# M5stamp_round_lcd.net
KiCad netlist of a schematic drawn in EAGLE
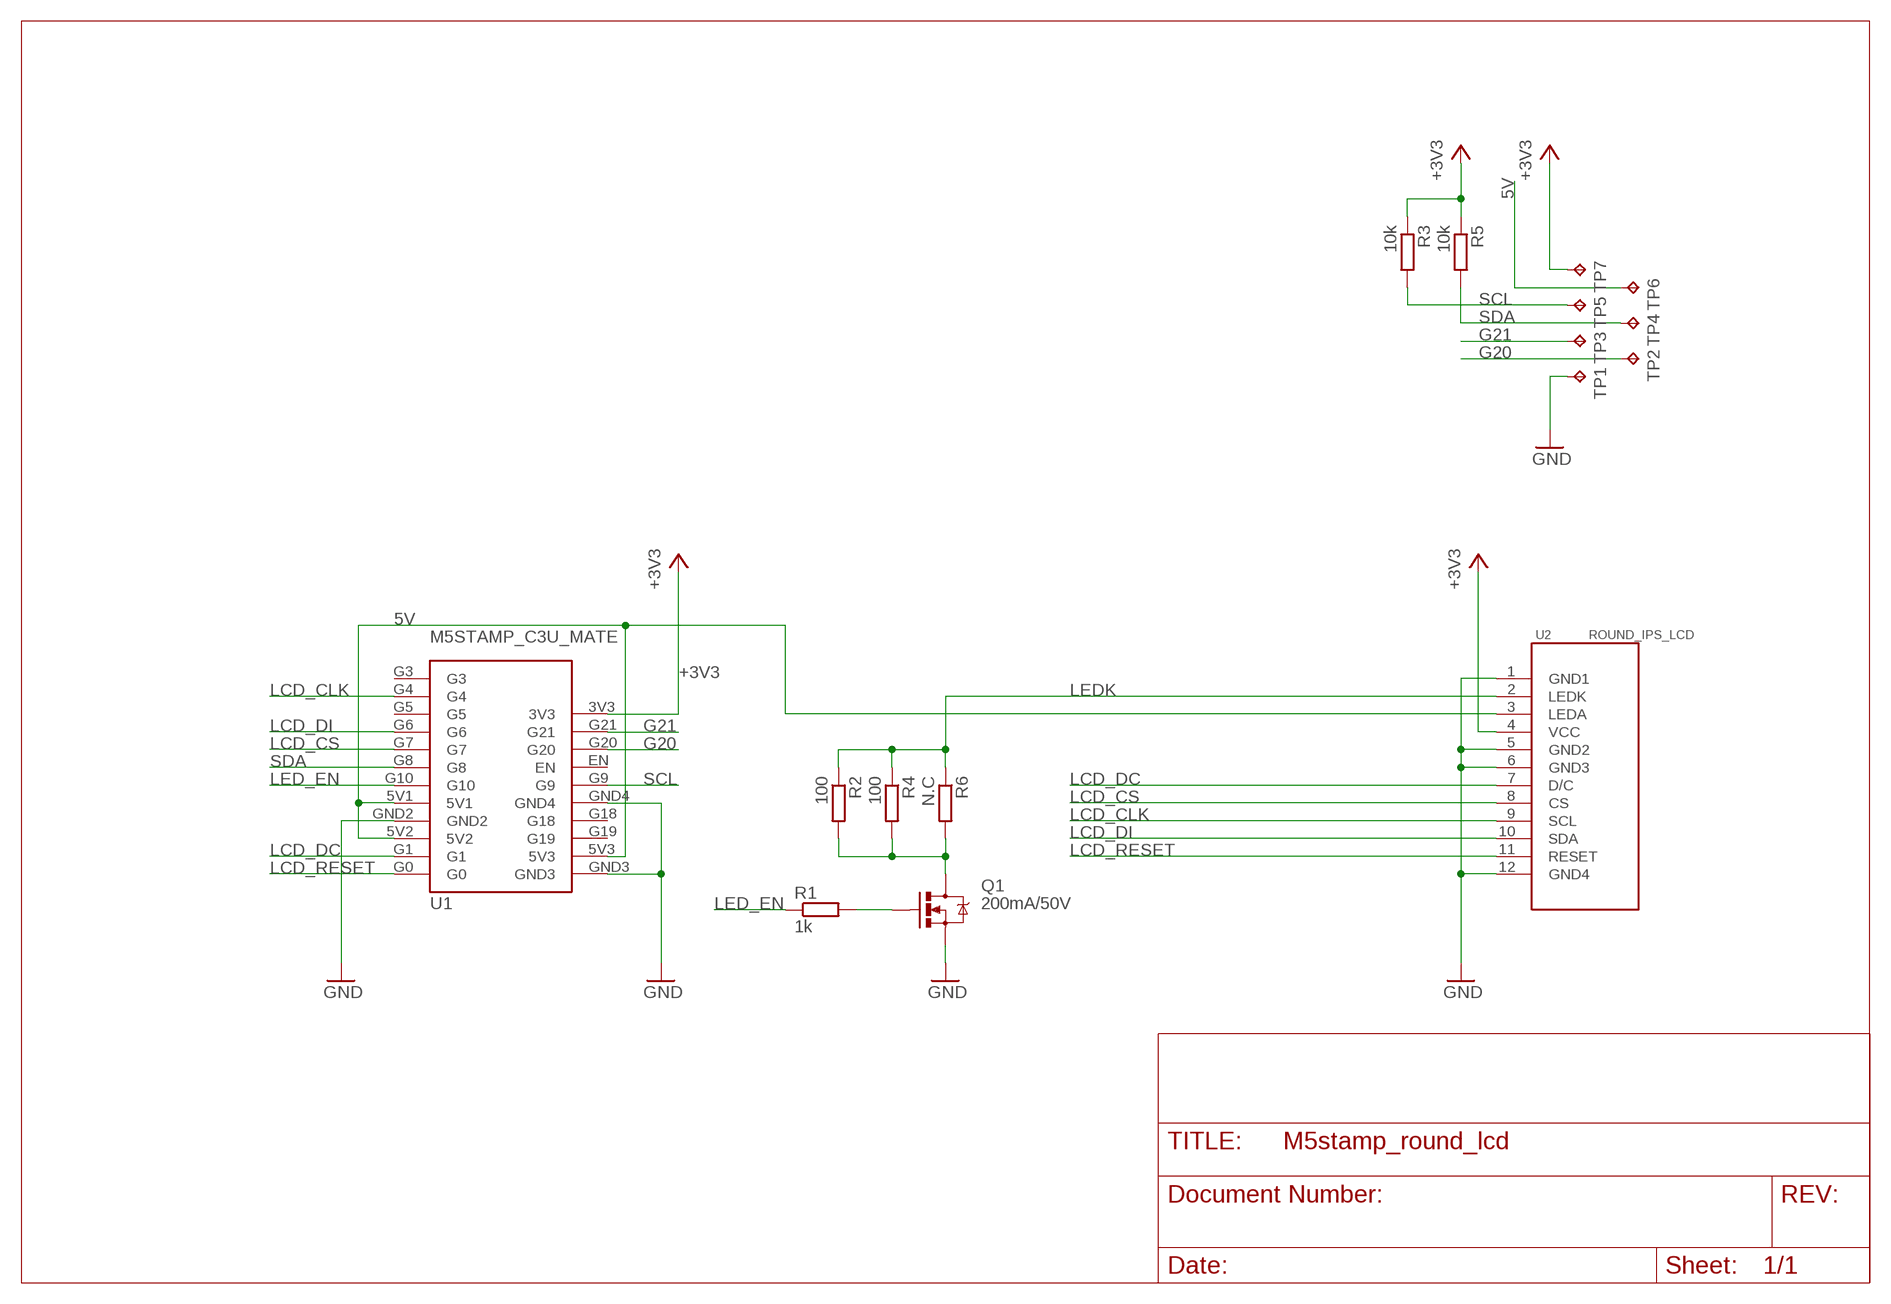
[diagram p0: schematic, sheet 1]

(export (version "E")
  (design (tool "Eeschema 10.0.6"))
  (components
    (comp (ref "Q1")
      (value "200mA/50V")
      (footprint "eagle-import:SOT23-3")
      (libsource (lib "eagle-import") (part "MOSFET-NCHANNELBSS138"))
    )
    (comp (ref "R1")
      (value "1k")
      (footprint "eagle-import:R0603")
      (libsource (lib "eagle-import") (part "R-EU_R0603"))
    )
    (comp (ref "R2")
      (value "100")
      (footprint "eagle-import:R0603")
      (libsource (lib "eagle-import") (part "R-EU_R0603"))
    )
    (comp (ref "R3")
      (value "10k")
      (footprint "eagle-import:R0603")
      (libsource (lib "eagle-import") (part "R-EU_R0603"))
    )
    (comp (ref "R4")
      (value "100")
      (footprint "eagle-import:R0603")
      (libsource (lib "eagle-import") (part "R-EU_R0603"))
    )
    (comp (ref "R5")
      (value "10k")
      (footprint "eagle-import:R0603")
      (libsource (lib "eagle-import") (part "R-EU_R0603"))
    )
    (comp (ref "R6")
      (value "N.C")
      (footprint "eagle-import:R0603")
      (libsource (lib "eagle-import") (part "R-EU_R0603"))
    )
    (comp (ref "TP1")
      (value "TPTP18R")
      (footprint "eagle-import:TP18R")
      (libsource (lib "eagle-import") (part "TPTP18R"))
    )
    (comp (ref "TP2")
      (value "TPTP18R")
      (footprint "eagle-import:TP18R")
      (libsource (lib "eagle-import") (part "TPTP18R"))
    )
    (comp (ref "TP3")
      (value "TPTP18R")
      (footprint "eagle-import:TP18R")
      (libsource (lib "eagle-import") (part "TPTP18R"))
    )
    (comp (ref "TP4")
      (value "TPTP18R")
      (footprint "eagle-import:TP18R")
      (libsource (lib "eagle-import") (part "TPTP18R"))
    )
    (comp (ref "TP5")
      (value "TPTP18R")
      (footprint "eagle-import:TP18R")
      (libsource (lib "eagle-import") (part "TPTP18R"))
    )
    (comp (ref "TP6")
      (value "TPTP18R")
      (footprint "eagle-import:TP18R")
      (libsource (lib "eagle-import") (part "TPTP18R"))
    )
    (comp (ref "TP7")
      (value "TPTP18R")
      (footprint "eagle-import:TP18R")
      (libsource (lib "eagle-import") (part "TPTP18R"))
    )
    (comp (ref "U1")
      (value "M5STAMP_C3U_MATE")
      (footprint "eagle-import:M5STAMPC3UMATE")
      (libsource (lib "eagle-import") (part "M5STAMP_C3U_MATE"))
    )
    (comp (ref "U2")
      (value "ROUND_IPS_LCD")
      (footprint "eagle-import:ROUND_IPS_LCD")
      (libsource (lib "eagle-import") (part "ROUND_IPS_LCD"))
    )
  )
  (nets
    (net (code "1") (name "+3V3") (class "Default")
      (node (ref "R3") (pin "1") (pinfunction "1_1") (pintype "passive"))
      (node (ref "R5") (pin "1") (pinfunction "1_1") (pintype "passive"))
      (node (ref "TP7") (pin "TP") (pinfunction "TP_TP") (pintype "input"))
      (node (ref "U1") (pin "3V3") (pinfunction "3V3_3V3") (pintype "bidirectional"))
      (node (ref "U2") (pin "4") (pinfunction "VCC_4") (pintype "power_in"))
    )
    (net (code "2") (name "/5V") (class "Default")
      (node (ref "TP6") (pin "TP") (pinfunction "TP_TP") (pintype "input"))
      (node (ref "U1") (pin "5V1") (pinfunction "5V1_5V1") (pintype "bidirectional"))
      (node (ref "U1") (pin "5V2") (pinfunction "5V2_5V2") (pintype "bidirectional"))
      (node (ref "U1") (pin "5V3") (pinfunction "5V3_5V3") (pintype "bidirectional"))
      (node (ref "U2") (pin "3") (pinfunction "LEDA_3") (pintype "bidirectional"))
    )
    (net (code "3") (name "/G20") (class "Default")
      (node (ref "TP2") (pin "TP") (pinfunction "TP_TP") (pintype "input"))
      (node (ref "U1") (pin "G20") (pinfunction "G20_G20") (pintype "bidirectional"))
    )
    (net (code "4") (name "/G21") (class "Default")
      (node (ref "TP3") (pin "TP") (pinfunction "TP_TP") (pintype "input"))
      (node (ref "U1") (pin "G21") (pinfunction "G21_G21") (pintype "bidirectional"))
    )
    (net (code "5") (name "/LCD_CLK") (class "Default")
      (node (ref "U1") (pin "G4") (pinfunction "G4_G4") (pintype "bidirectional"))
      (node (ref "U2") (pin "9") (pinfunction "SCL_9") (pintype "input"))
    )
    (net (code "6") (name "/LCD_CS") (class "Default")
      (node (ref "U1") (pin "G7") (pinfunction "G7_G7") (pintype "bidirectional"))
      (node (ref "U2") (pin "8") (pinfunction "CS_8") (pintype "input"))
    )
    (net (code "7") (name "/LCD_DC") (class "Default")
      (node (ref "U1") (pin "G1") (pinfunction "G1_G1") (pintype "bidirectional"))
      (node (ref "U2") (pin "7") (pinfunction "D/C_7") (pintype "input"))
    )
    (net (code "8") (name "/LCD_DI") (class "Default")
      (node (ref "U1") (pin "G6") (pinfunction "G6_G6") (pintype "bidirectional"))
      (node (ref "U2") (pin "10") (pinfunction "SDA_10") (pintype "bidirectional"))
    )
    (net (code "9") (name "/LCD_RESET") (class "Default")
      (node (ref "U1") (pin "G0") (pinfunction "G0_G0") (pintype "bidirectional"))
      (node (ref "U2") (pin "11") (pinfunction "RESET_11") (pintype "input"))
    )
    (net (code "10") (name "/LEDK") (class "Default")
      (node (ref "R2") (pin "1") (pinfunction "1_1") (pintype "passive"))
      (node (ref "R4") (pin "1") (pinfunction "1_1") (pintype "passive"))
      (node (ref "R6") (pin "1") (pinfunction "1_1") (pintype "passive"))
      (node (ref "U2") (pin "2") (pinfunction "LEDK_2") (pintype "bidirectional"))
    )
    (net (code "11") (name "/LED_EN") (class "Default")
      (node (ref "R1") (pin "1") (pinfunction "1_1") (pintype "passive"))
      (node (ref "U1") (pin "G10") (pinfunction "G10_G10") (pintype "bidirectional"))
    )
    (net (code "12") (name "/SCL") (class "Default")
      (node (ref "R3") (pin "2") (pinfunction "2_2") (pintype "passive"))
      (node (ref "TP5") (pin "TP") (pinfunction "TP_TP") (pintype "input"))
      (node (ref "U1") (pin "G9") (pinfunction "G9_G9") (pintype "bidirectional"))
    )
    (net (code "13") (name "/SDA") (class "Default")
      (node (ref "R5") (pin "2") (pinfunction "2_2") (pintype "passive"))
      (node (ref "TP4") (pin "TP") (pinfunction "TP_TP") (pintype "input"))
      (node (ref "U1") (pin "G8") (pinfunction "G8_G8") (pintype "bidirectional"))
    )
    (net (code "14") (name "GND") (class "Default")
      (node (ref "Q1") (pin "2") (pinfunction "S_2") (pintype "passive"))
      (node (ref "TP1") (pin "TP") (pinfunction "TP_TP") (pintype "input"))
      (node (ref "U1") (pin "GND2") (pinfunction "GND2_GND2") (pintype "bidirectional"))
      (node (ref "U1") (pin "GND3") (pinfunction "GND3_GND3") (pintype "bidirectional"))
      (node (ref "U1") (pin "GND4") (pinfunction "GND4_GND4") (pintype "bidirectional"))
      (node (ref "U2") (pin "1") (pinfunction "GND1_1") (pintype "power_in"))
      (node (ref "U2") (pin "12") (pinfunction "GND4_12") (pintype "power_in"))
      (node (ref "U2") (pin "5") (pinfunction "GND2_5") (pintype "power_in"))
      (node (ref "U2") (pin "6") (pinfunction "GND3_6") (pintype "power_in"))
    )
    (net (code "15") (name "Net-(Q1-D)") (class "Default")
      (node (ref "Q1") (pin "3") (pinfunction "D_3") (pintype "passive"))
      (node (ref "R2") (pin "2") (pinfunction "2_2") (pintype "passive"))
      (node (ref "R4") (pin "2") (pinfunction "2_2") (pintype "passive"))
      (node (ref "R6") (pin "2") (pinfunction "2_2") (pintype "passive"))
    )
    (net (code "16") (name "Net-(Q1-G)") (class "Default")
      (node (ref "Q1") (pin "1") (pinfunction "G_1") (pintype "passive"))
      (node (ref "R1") (pin "2") (pinfunction "2_2") (pintype "passive"))
    )
    (net (code "17") (name "unconnected-(U1-PadEN)") (class "Default")
      (node (ref "U1") (pin "EN") (pinfunction "EN_EN") (pintype "bidirectional"))
    )
    (net (code "18") (name "unconnected-(U1-PadG3)") (class "Default")
      (node (ref "U1") (pin "G3") (pinfunction "G3_G3") (pintype "bidirectional"))
    )
    (net (code "19") (name "unconnected-(U1-PadG5)") (class "Default")
      (node (ref "U1") (pin "G5") (pinfunction "G5_G5") (pintype "bidirectional"))
    )
    (net (code "20") (name "unconnected-(U1-PadG18)") (class "Default")
      (node (ref "U1") (pin "G18") (pinfunction "G18_G18") (pintype "bidirectional"))
    )
    (net (code "21") (name "unconnected-(U1-PadG19)") (class "Default")
      (node (ref "U1") (pin "G19") (pinfunction "G19_G19") (pintype "bidirectional"))
    )
  )
)
